# telemtryWing.net
KiCad netlist of a schematic drawn in EAGLE
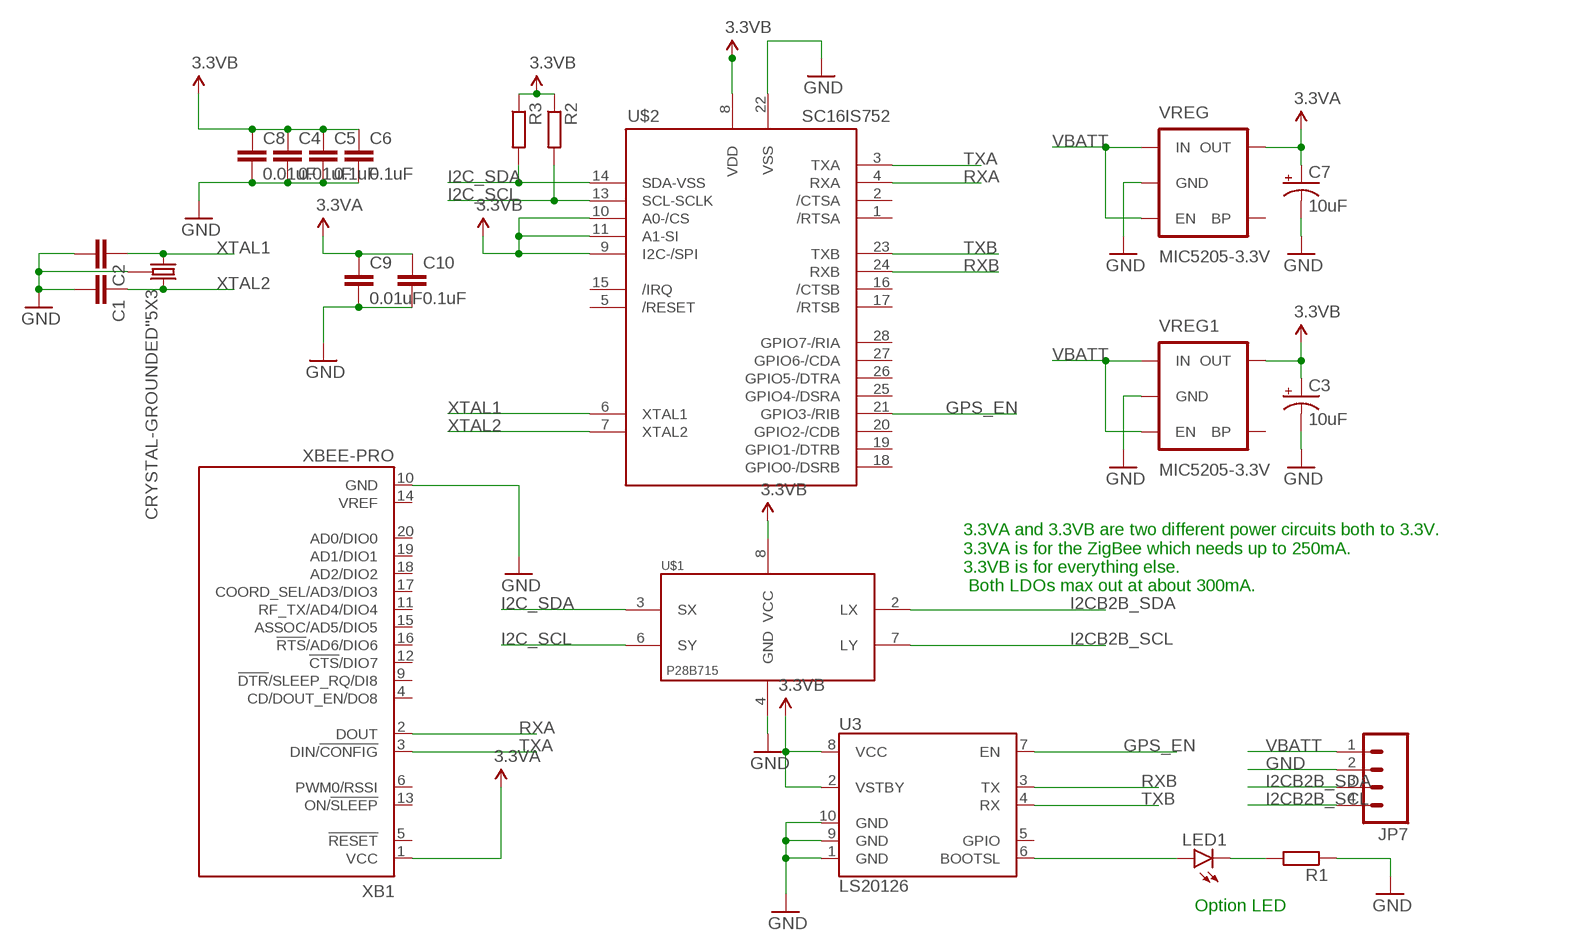
[diagram p0: schematic, sheet 1]

(export (version "E")
  (design (tool "Eeschema 10.0.6"))
  (components
    (comp (ref "C1")
      (value "C0603")
      (footprint "eagle-import:C0603")
      (libsource (lib "eagle-import") (part "C0603"))
    )
    (comp (ref "C2")
      (value "C0603")
      (footprint "eagle-import:C0603")
      (libsource (lib "eagle-import") (part "C0603"))
    )
    (comp (ref "C3")
      (value "10uF")
      (footprint "eagle-import:EIA3216")
      (libsource (lib "eagle-import") (part "CAP_POL1206"))
    )
    (comp (ref "C4")
      (value "0.01uF")
      (footprint "eagle-import:C0603")
      (libsource (lib "eagle-import") (part "C0603"))
    )
    (comp (ref "C5")
      (value "0.1uF")
      (footprint "eagle-import:C0603")
      (libsource (lib "eagle-import") (part "C0603"))
    )
    (comp (ref "C6")
      (value "0.1uF")
      (footprint "eagle-import:C0603")
      (libsource (lib "eagle-import") (part "C0603"))
    )
    (comp (ref "C7")
      (value "10uF")
      (footprint "eagle-import:EIA3216")
      (libsource (lib "eagle-import") (part "CAP_POL1206"))
    )
    (comp (ref "C8")
      (value "0.01uF")
      (footprint "eagle-import:C0603")
      (libsource (lib "eagle-import") (part "C0603"))
    )
    (comp (ref "C9")
      (value "0.01uF")
      (footprint "eagle-import:C0603")
      (libsource (lib "eagle-import") (part "C0603"))
    )
    (comp (ref "C10")
      (value "0.1uF")
      (footprint "eagle-import:C0603")
      (libsource (lib "eagle-import") (part "C0603"))
    )
    (comp (ref "JP7")
      (value "M04JST")
      (footprint "eagle-import:1X04-1.5MM_JST")
      (libsource (lib "eagle-import") (part "M04JST"))
    )
    (comp (ref "LED1")
      (value "LED0603")
      (footprint "eagle-import:LED-0603")
      (libsource (lib "eagle-import") (part "LED0603"))
    )
    (comp (ref "R1")
      (value "R0603")
      (footprint "eagle-import:R0603")
      (libsource (lib "eagle-import") (part "R0603"))
    )
    (comp (ref "R2")
      (value "R0603")
      (footprint "eagle-import:R0603")
      (libsource (lib "eagle-import") (part "R0603"))
    )
    (comp (ref "R3")
      (value "R0603")
      (footprint "eagle-import:R0603")
      (libsource (lib "eagle-import") (part "R0603"))
    )
    (comp (ref "U$1")
      (value "P82B715")
      (footprint "eagle-import:SO8")
      (libsource (lib "eagle-import") (part "P82B715"))
    )
    (comp (ref "U$2")
      (value "SC16IS752")
      (footprint "eagle-import:TSSOP28")
      (libsource (lib "eagle-import") (part "SC16IS752"))
    )
    (comp (ref "U$3")
      (value "CRYSTAL-GROUNDED''5X3")
      (footprint "eagle-import:CRYSTAL-SMD-5X3")
      (libsource (lib "eagle-import") (part "CRYSTAL-GROUNDED''5X3"))
    )
    (comp (ref "U3")
      (value "LS20126")
      (footprint "eagle-import:LS20126")
      (libsource (lib "eagle-import") (part "LS20126"))
    )
    (comp (ref "VREG")
      (value "MIC5205-3.3V")
      (footprint "eagle-import:SOT23-5")
      (libsource (lib "eagle-import") (part "V_REG_LDOSMD"))
    )
    (comp (ref "VREG1")
      (value "MIC5205-3.3V")
      (footprint "eagle-import:SOT23-5")
      (libsource (lib "eagle-import") (part "V_REG_LDOSMD"))
    )
    (comp (ref "XB1")
      (value "XBEE-PRO")
      (footprint "eagle-import:XBEE-PRO")
      (fields (field (name "MPN") "XBP24-AWI-001"))
      (libsource (lib "eagle-import") (part "XBEE-PRO"))
    )
  )
  (nets
    (net (code "1") (name "/GPS_EN") (class "Default")
      (node (ref "U$2") (pin "21") (pinfunction "GPIO3-/RIB_21") (pintype "bidirectional"))
      (node (ref "U3") (pin "7") (pinfunction "EN_7") (pintype "bidirectional"))
    )
    (net (code "2") (name "/I2CB2B_SCL") (class "Default")
      (node (ref "JP7") (pin "4") (pinfunction "4_4") (pintype "passive"))
      (node (ref "U$1") (pin "7") (pinfunction "LY_7") (pintype "bidirectional"))
    )
    (net (code "3") (name "/I2CB2B_SDA") (class "Default")
      (node (ref "JP7") (pin "3") (pinfunction "3_3") (pintype "passive"))
      (node (ref "U$1") (pin "2") (pinfunction "LX_2") (pintype "bidirectional"))
    )
    (net (code "4") (name "/I2C_SCL") (class "Default")
      (node (ref "R2") (pin "2") (pinfunction "2_2") (pintype "passive"))
      (node (ref "U$1") (pin "6") (pinfunction "SY_6") (pintype "bidirectional"))
      (node (ref "U$2") (pin "13") (pinfunction "SCL-SCLK_13") (pintype "bidirectional"))
    )
    (net (code "5") (name "/I2C_SDA") (class "Default")
      (node (ref "R3") (pin "2") (pinfunction "2_2") (pintype "passive"))
      (node (ref "U$1") (pin "3") (pinfunction "SX_3") (pintype "bidirectional"))
      (node (ref "U$2") (pin "14") (pinfunction "SDA-VSS_14") (pintype "bidirectional"))
    )
    (net (code "6") (name "/RXA") (class "Default")
      (node (ref "U$2") (pin "4") (pinfunction "RXA_4") (pintype "bidirectional"))
      (node (ref "XB1") (pin "2") (pinfunction "DOUT_2") (pintype "output"))
    )
    (net (code "7") (name "/RXB") (class "Default")
      (node (ref "U$2") (pin "24") (pinfunction "RXB_24") (pintype "bidirectional"))
      (node (ref "U3") (pin "3") (pinfunction "TX_3") (pintype "bidirectional"))
    )
    (net (code "8") (name "/TXA") (class "Default")
      (node (ref "U$2") (pin "3") (pinfunction "TXA_3") (pintype "bidirectional"))
      (node (ref "XB1") (pin "3") (pinfunction "DIN/~{CONFIG}_3") (pintype "input"))
    )
    (net (code "9") (name "/TXB") (class "Default")
      (node (ref "U$2") (pin "23") (pinfunction "TXB_23") (pintype "bidirectional"))
      (node (ref "U3") (pin "4") (pinfunction "RX_4") (pintype "bidirectional"))
    )
    (net (code "10") (name "/VBATT") (class "Default")
      (node (ref "JP7") (pin "1") (pinfunction "1_1") (pintype "passive"))
      (node (ref "VREG") (pin "1") (pinfunction "IN_1") (pintype "input"))
      (node (ref "VREG") (pin "3") (pinfunction "EN_3") (pintype "input"))
      (node (ref "VREG1") (pin "1") (pinfunction "IN_1") (pintype "input"))
      (node (ref "VREG1") (pin "3") (pinfunction "EN_3") (pintype "input"))
    )
    (net (code "11") (name "/XTAL1") (class "Default")
      (node (ref "C2") (pin "1") (pinfunction "1_1") (pintype "passive"))
      (node (ref "U$2") (pin "6") (pinfunction "XTAL1_6") (pintype "bidirectional"))
      (node (ref "U$3") (pin "3") (pinfunction "1_3") (pintype "passive"))
    )
    (net (code "12") (name "/XTAL2") (class "Default")
      (node (ref "C1") (pin "1") (pinfunction "1_1") (pintype "passive"))
      (node (ref "U$2") (pin "7") (pinfunction "XTAL2_7") (pintype "bidirectional"))
      (node (ref "U$3") (pin "1") (pinfunction "2_1") (pintype "passive"))
    )
    (net (code "13") (name "3.3VA") (class "Default")
      (node (ref "C10") (pin "1") (pinfunction "1_1") (pintype "passive"))
      (node (ref "C7") (pin "A") (pinfunction "+_A") (pintype "passive"))
      (node (ref "C9") (pin "1") (pinfunction "1_1") (pintype "passive"))
      (node (ref "VREG") (pin "5") (pinfunction "OUT_5") (pintype "passive"))
      (node (ref "XB1") (pin "1") (pinfunction "VCC_1") (pintype "power_in"))
    )
    (net (code "14") (name "3.3VB") (class "Default")
      (node (ref "C3") (pin "A") (pinfunction "+_A") (pintype "passive"))
      (node (ref "C4") (pin "1") (pinfunction "1_1") (pintype "passive"))
      (node (ref "C5") (pin "1") (pinfunction "1_1") (pintype "passive"))
      (node (ref "C6") (pin "1") (pinfunction "1_1") (pintype "passive"))
      (node (ref "C8") (pin "1") (pinfunction "1_1") (pintype "passive"))
      (node (ref "R2") (pin "1") (pinfunction "1_1") (pintype "passive"))
      (node (ref "R3") (pin "1") (pinfunction "1_1") (pintype "passive"))
      (node (ref "U$1") (pin "8") (pinfunction "VCC_8") (pintype "bidirectional"))
      (node (ref "U$2") (pin "10") (pinfunction "A0-/CS_10") (pintype "bidirectional"))
      (node (ref "U$2") (pin "11") (pinfunction "A1-SI_11") (pintype "bidirectional"))
      (node (ref "U$2") (pin "8") (pinfunction "VDD_8") (pintype "bidirectional"))
      (node (ref "U$2") (pin "9") (pinfunction "I2C-/SPI_9") (pintype "bidirectional"))
      (node (ref "U3") (pin "2") (pinfunction "VSTBY_2") (pintype "bidirectional"))
      (node (ref "U3") (pin "8") (pinfunction "VCC_8") (pintype "bidirectional"))
      (node (ref "VREG1") (pin "5") (pinfunction "OUT_5") (pintype "passive"))
    )
    (net (code "15") (name "GND") (class "Default")
      (node (ref "C1") (pin "2") (pinfunction "2_2") (pintype "passive"))
      (node (ref "C10") (pin "2") (pinfunction "2_2") (pintype "passive"))
      (node (ref "C2") (pin "2") (pinfunction "2_2") (pintype "passive"))
      (node (ref "C3") (pin "C") (pinfunction "-_C") (pintype "passive"))
      (node (ref "C4") (pin "2") (pinfunction "2_2") (pintype "passive"))
      (node (ref "C5") (pin "2") (pinfunction "2_2") (pintype "passive"))
      (node (ref "C6") (pin "2") (pinfunction "2_2") (pintype "passive"))
      (node (ref "C7") (pin "C") (pinfunction "-_C") (pintype "passive"))
      (node (ref "C8") (pin "2") (pinfunction "2_2") (pintype "passive"))
      (node (ref "C9") (pin "2") (pinfunction "2_2") (pintype "passive"))
      (node (ref "JP7") (pin "2") (pinfunction "2_2") (pintype "passive"))
      (node (ref "R1") (pin "1") (pinfunction "1_1") (pintype "passive"))
      (node (ref "U$1") (pin "4") (pinfunction "GND_4") (pintype "bidirectional"))
      (node (ref "U$2") (pin "22") (pinfunction "VSS_22") (pintype "bidirectional"))
      (node (ref "U$3") (pin "2") (pinfunction "3_2") (pintype "passive"))
      (node (ref "U$3") (pin "4") (pinfunction "3_4") (pintype "passive"))
      (node (ref "U3") (pin "1") (pinfunction "GND_1") (pintype "bidirectional"))
      (node (ref "U3") (pin "10") (pinfunction "GND_10") (pintype "bidirectional"))
      (node (ref "U3") (pin "9") (pinfunction "GND_9") (pintype "bidirectional"))
      (node (ref "VREG") (pin "2") (pinfunction "GND_2") (pintype "input"))
      (node (ref "VREG1") (pin "2") (pinfunction "GND_2") (pintype "input"))
      (node (ref "XB1") (pin "10") (pinfunction "GND_10") (pintype "power_in"))
    )
    (net (code "16") (name "Net-(LED1-PadC)") (class "Default")
      (node (ref "LED1") (pin "C") (pinfunction "C_C") (pintype "passive"))
      (node (ref "R1") (pin "2") (pinfunction "2_2") (pintype "passive"))
    )
    (net (code "17") (name "Net-(U3-BOOTSL)") (class "Default")
      (node (ref "LED1") (pin "A") (pinfunction "A_A") (pintype "passive"))
      (node (ref "U3") (pin "6") (pinfunction "BOOTSL_6") (pintype "bidirectional"))
    )
    (net (code "18") (name "unconnected-(U$2-GPIO0-{slash}DSRB-Pad18)") (class "Default")
      (node (ref "U$2") (pin "18") (pinfunction "GPIO0-/DSRB_18") (pintype "bidirectional"))
    )
    (net (code "19") (name "unconnected-(U$2-GPIO1-{slash}DTRB-Pad19)") (class "Default")
      (node (ref "U$2") (pin "19") (pinfunction "GPIO1-/DTRB_19") (pintype "bidirectional"))
    )
    (net (code "20") (name "unconnected-(U$2-GPIO2-{slash}CDB-Pad20)") (class "Default")
      (node (ref "U$2") (pin "20") (pinfunction "GPIO2-/CDB_20") (pintype "bidirectional"))
    )
    (net (code "21") (name "unconnected-(U$2-GPIO4-{slash}DSRA-Pad25)") (class "Default")
      (node (ref "U$2") (pin "25") (pinfunction "GPIO4-/DSRA_25") (pintype "bidirectional"))
    )
    (net (code "22") (name "unconnected-(U$2-GPIO5-{slash}DTRA-Pad26)") (class "Default")
      (node (ref "U$2") (pin "26") (pinfunction "GPIO5-/DTRA_26") (pintype "bidirectional"))
    )
    (net (code "23") (name "unconnected-(U$2-GPIO6-{slash}CDA-Pad27)") (class "Default")
      (node (ref "U$2") (pin "27") (pinfunction "GPIO6-/CDA_27") (pintype "bidirectional"))
    )
    (net (code "24") (name "unconnected-(U$2-GPIO7-{slash}RIA-Pad28)") (class "Default")
      (node (ref "U$2") (pin "28") (pinfunction "GPIO7-/RIA_28") (pintype "bidirectional"))
    )
    (net (code "25") (name "unconnected-(U$2-{slash}CTSA-Pad2)") (class "Default")
      (node (ref "U$2") (pin "2") (pinfunction "/CTSA_2") (pintype "bidirectional"))
    )
    (net (code "26") (name "unconnected-(U$2-{slash}CTSB-Pad16)") (class "Default")
      (node (ref "U$2") (pin "16") (pinfunction "/CTSB_16") (pintype "bidirectional"))
    )
    (net (code "27") (name "unconnected-(U$2-{slash}IRQ-Pad15)") (class "Default")
      (node (ref "U$2") (pin "15") (pinfunction "/IRQ_15") (pintype "bidirectional"))
    )
    (net (code "28") (name "unconnected-(U$2-{slash}RESET-Pad5)") (class "Default")
      (node (ref "U$2") (pin "5") (pinfunction "/RESET_5") (pintype "bidirectional"))
    )
    (net (code "29") (name "unconnected-(U$2-{slash}RTSA-Pad1)") (class "Default")
      (node (ref "U$2") (pin "1") (pinfunction "/RTSA_1") (pintype "bidirectional"))
    )
    (net (code "30") (name "unconnected-(U$2-{slash}RTSB-Pad17)") (class "Default")
      (node (ref "U$2") (pin "17") (pinfunction "/RTSB_17") (pintype "bidirectional"))
    )
    (net (code "31") (name "unconnected-(U3-GPIO-Pad5)") (class "Default")
      (node (ref "U3") (pin "5") (pinfunction "GPIO_5") (pintype "bidirectional"))
    )
    (net (code "32") (name "unconnected-(VREG-BP-Pad4)") (class "Default")
      (node (ref "VREG") (pin "4") (pinfunction "BP_4") (pintype "input"))
    )
    (net (code "33") (name "unconnected-(VREG1-BP-Pad4)") (class "Default")
      (node (ref "VREG1") (pin "4") (pinfunction "BP_4") (pintype "input"))
    )
    (net (code "34") (name "unconnected-(XB1-AD0{slash}DIO0-Pad20)") (class "Default")
      (node (ref "XB1") (pin "20") (pinfunction "AD0/DIO0_20") (pintype "bidirectional"))
    )
    (net (code "35") (name "unconnected-(XB1-AD1{slash}DIO1-Pad19)") (class "Default")
      (node (ref "XB1") (pin "19") (pinfunction "AD1/DIO1_19") (pintype "bidirectional"))
    )
    (net (code "36") (name "unconnected-(XB1-AD2{slash}DIO2-Pad18)") (class "Default")
      (node (ref "XB1") (pin "18") (pinfunction "AD2/DIO2_18") (pintype "bidirectional"))
    )
    (net (code "37") (name "unconnected-(XB1-ASSOC{slash}AD5{slash}DIO5-Pad15)") (class "Default")
      (node (ref "XB1") (pin "15") (pinfunction "ASSOC/AD5/DIO5_15") (pintype "bidirectional"))
    )
    (net (code "38") (name "unconnected-(XB1-CD{slash}DOUT_EN{slash}DO8-Pad4)") (class "Default")
      (node (ref "XB1") (pin "4") (pinfunction "CD/DOUT_EN/DO8_4") (pintype "output"))
    )
    (net (code "39") (name "unconnected-(XB1-COORD_SEL{slash}AD3{slash}DIO3-Pad17)") (class "Default")
      (node (ref "XB1") (pin "17") (pinfunction "COORD_SEL/AD3/DIO3_17") (pintype "bidirectional"))
    )
    (net (code "40") (name "unconnected-(XB1-ON{slash}~{SLEEP}-Pad13)") (class "Default")
      (node (ref "XB1") (pin "13") (pinfunction "ON/~{SLEEP}_13") (pintype "output"))
    )
    (net (code "41") (name "unconnected-(XB1-PWM0{slash}RSSI-Pad6)") (class "Default")
      (node (ref "XB1") (pin "6") (pinfunction "PWM0/RSSI_6") (pintype "output"))
    )
    (net (code "42") (name "unconnected-(XB1-RF_TX{slash}AD4{slash}DIO4-Pad11)") (class "Default")
      (node (ref "XB1") (pin "11") (pinfunction "RF_TX/AD4/DIO4_11") (pintype "bidirectional"))
    )
    (net (code "43") (name "unconnected-(XB1-VREF-Pad14)") (class "Default")
      (node (ref "XB1") (pin "14") (pinfunction "VREF_14") (pintype "input"))
    )
    (net (code "44") (name "unconnected-(XB1-~{CTS}{slash}DIO7-Pad12)") (class "Default")
      (node (ref "XB1") (pin "12") (pinfunction "~{CTS}/DIO7_12") (pintype "bidirectional"))
    )
    (net (code "45") (name "unconnected-(XB1-~{DTR}{slash}SLEEP_RQ{slash}DI8-Pad9)") (class "Default")
      (node (ref "XB1") (pin "9") (pinfunction "~{DTR}/SLEEP_RQ/DI8_9") (pintype "bidirectional"))
    )
    (net (code "46") (name "unconnected-(XB1-~{RESET}-Pad5)") (class "Default")
      (node (ref "XB1") (pin "5") (pinfunction "~{RESET}_5") (pintype "input"))
    )
    (net (code "47") (name "unconnected-(XB1-~{RTS}{slash}AD6{slash}DIO6-Pad16)") (class "Default")
      (node (ref "XB1") (pin "16") (pinfunction "~{RTS}/AD6/DIO6_16") (pintype "bidirectional"))
    )
  )
)
